# SD.net
KiCad netlist of a schematic drawn in Altium Designer
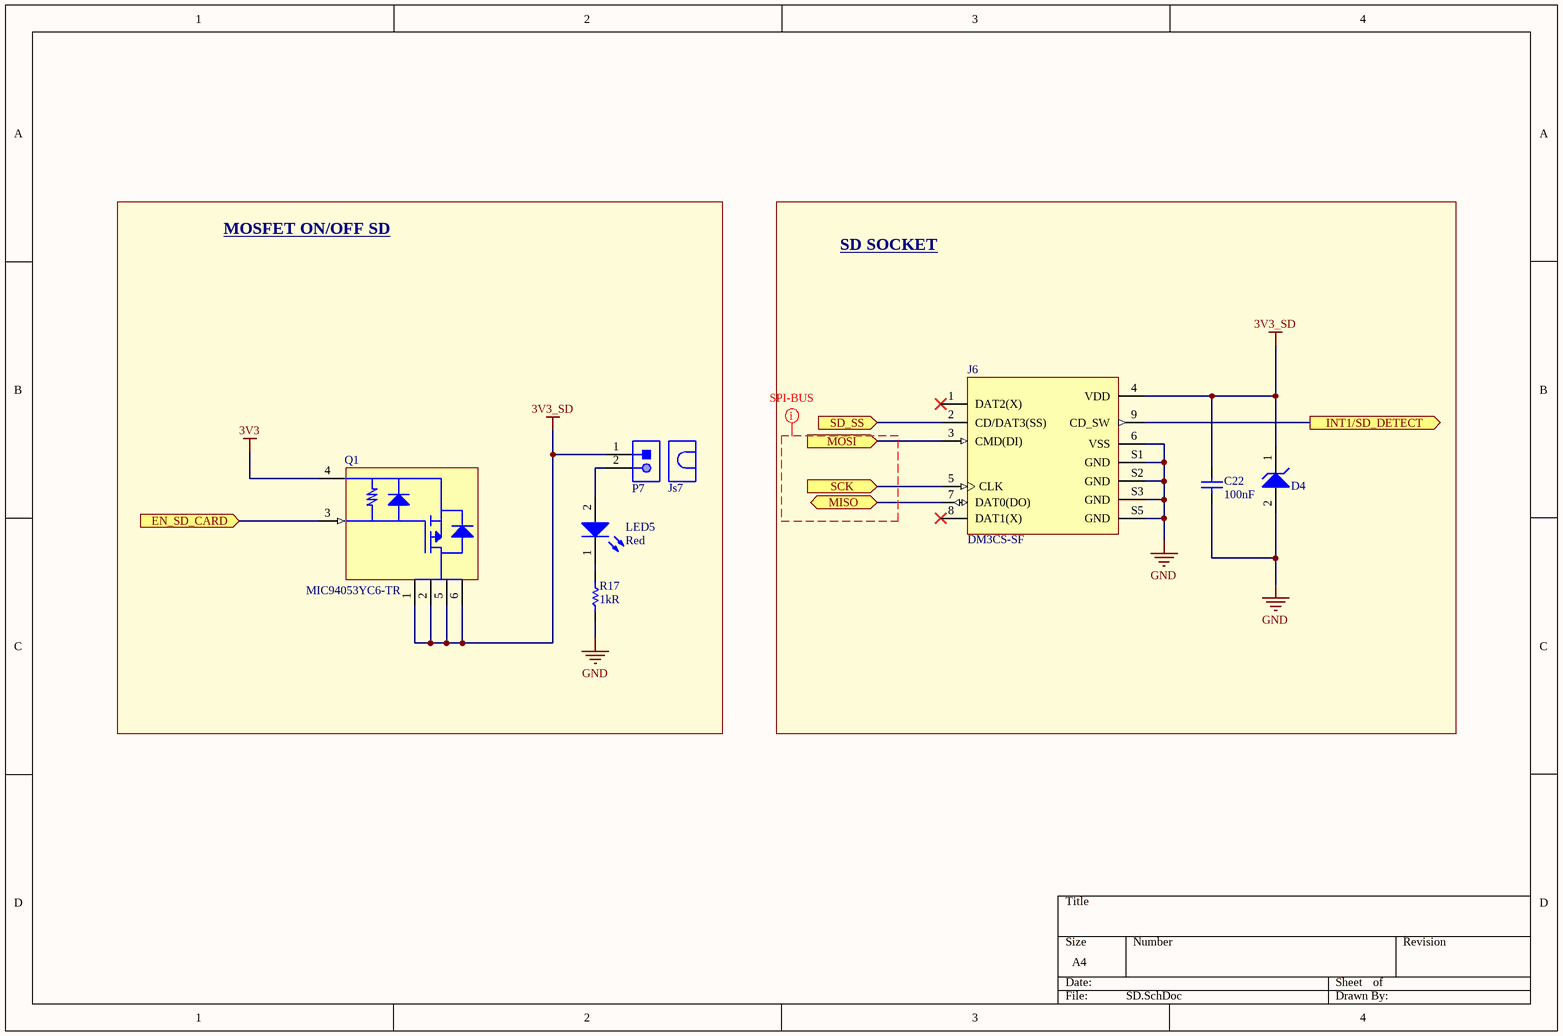
[diagram p0: SD.SchDoc]

(export (version "E")
  (design (tool "Eeschema 10.0.6"))
  (components
    (comp (ref "C22")
      (value "100nF")
      (footprint "Cap 0805 (2012 Metric)")
      (fields
        (field (name "MANUFACTURER") "Yageo")
        (field (name "MANUFACTURER PART NUMBER") "CC0805ZRY5V9BB104")
        (field (name "TOLERANCE") "80%")
      )
      (libsource (lib "Daniel_Integrated_Library") (part "Capacitor"))
    )
    (comp (ref "D4")
      (value "Diode")
      (footprint "Diode SOD123")
      (description "DIODE GEN PURP 75V 150MA 0603")
      (fields
        (field (name "MANUFACTURER") "Taiwan Semiconductor")
        (field (name "MANUFACTURER PART NUMBER") "TS4148CRZG")
      )
      (libsource (lib "Daniel_Integrated_Library") (part "Diode"))
    )
    (comp (ref "J6")
      (value "DM3CS-SF")
      (footprint "SDHolder")
      (description "10 (8 + 2) Position Card Connector Secure Digital - microSD™ Surface Mount, Right Angle Gold")
      (fields (field (name "MANUFACTURER") "Hirose"))
      (libsource (lib "Daniel_Integrated_Library") (part "SDHolder"))
    )
    (comp (ref "Js7")
      (value "Jumper (2x1)")
      (footprint "Header JMP 2x1")
      (description "2 (1 x 2) Position Shunt Connector Black Open Top 0.100\" (2.54mm) Gold")
      (fields
        (field (name "MANUFACTURER") "Sullins")
        (field (name "MANUFACTURER PART NUMBER") "QPC02SXGN-RC")
      )
      (libsource (lib "Daniel_Integrated_Library") (part "Jumper (2x1)"))
    )
    (comp (ref "LED5")
      (value "Red")
      (footprint "LED 0805(2012 METRIC)")
      (description "SMD LED red 2.4 V 0805, 150080RS75000, Würth Elektronik")
      (fields
        (field (name "MANUFACTURER") "Wurth Electronics")
        (field (name "MANUFACTURER PART NUMBER") "150080RS75000")
      )
      (libsource (lib "Daniel_Integrated_Library") (part "LED"))
    )
    (comp (ref "P7")
      (value "Header 2x1")
      (footprint "Header 2x1")
      (description "Connector Header Through Hole 2 position 0.100\" (2.54mm)")
      (fields
        (field (name "MANUFACTURER") "Amphenol FCI")
        (field (name "MANUFACTURER PART NUMBER") "68001-402HLF")
      )
      (libsource (lib "Daniel_Integrated_Library") (part "Header 2x1"))
    )
    (comp (ref "Q1")
      (value "MIC94053YC6-TR")
      (footprint "SC-70-6")
      (description "P-Channel 6V 2A (Ta) 270mW (Ta) Surface Mount SC-70-6")
      (fields (field (name "MANUFACTURER") "Microchip"))
      (libsource (lib "Daniel_Integrated_Library") (part "TransistorMosfet(Load)"))
    )
    (comp (ref "R17")
      (value "1kR")
      (footprint "Res 0805 (2012 Metric)")
      (description "RES 1K OHM 1% 1/4W 0805")
      (fields
        (field (name "MANUFACTURER") "Stackpole Electronics")
        (field (name "MANUFACTURER PART NUMBER") "RNCP0805FTD1K00")
      )
      (libsource (lib "Daniel_Integrated_Library") (part "Resistor"))
    )
  )
  (nets
    (net (code "1") (name "/EN_SD_CARD") (class "Default")
      (node (ref "Q1") (pin "3") (pinfunction "G_3") (pintype "input"))
    )
    (net (code "2") (name "/INT1{slash}SD_DETECT") (class "Default")
      (node (ref "J6") (pin "9") (pinfunction "CD_SW_9") (pintype "output"))
    )
    (net (code "3") (name "/MISO") (class "Default")
      (node (ref "J6") (pin "7") (pinfunction "DAT0(DO)_7") (pintype "bidirectional"))
    )
    (net (code "4") (name "/MOSI") (class "Default")
      (node (ref "J6") (pin "3") (pinfunction "CMD(DI)_3") (pintype "input"))
    )
    (net (code "5") (name "/SCK") (class "Default")
      (node (ref "J6") (pin "5") (pinfunction "CLK_5") (pintype "input"))
    )
    (net (code "6") (name "/SD_SS") (class "Default")
      (node (ref "J6") (pin "2") (pinfunction "CD/DAT3(SS)_2") (pintype "passive"))
    )
    (net (code "7") (name "3V3") (class "Default")
      (node (ref "Q1") (pin "4") (pinfunction "S_4") (pintype "passive"))
    )
    (net (code "8") (name "3V3_SD") (class "Default")
      (node (ref "C22") (pin "1") (pinfunction "1_1") (pintype "passive"))
      (node (ref "D4") (pin "1") (pinfunction "K_1") (pintype "passive"))
      (node (ref "J6") (pin "4") (pinfunction "VDD_4") (pintype "passive"))
      (node (ref "P7") (pin "1") (pinfunction "1_1") (pintype "passive"))
      (node (ref "Q1") (pin "1") (pinfunction "D_1") (pintype "passive"))
      (node (ref "Q1") (pin "2") (pinfunction "D_2") (pintype "passive"))
      (node (ref "Q1") (pin "5") (pinfunction "D_5") (pintype "passive"))
      (node (ref "Q1") (pin "6") (pinfunction "D_6") (pintype "passive"))
    )
    (net (code "9") (name "GND") (class "Default")
      (node (ref "C22") (pin "2") (pinfunction "2_2") (pintype "passive"))
      (node (ref "D4") (pin "2") (pinfunction "A_2") (pintype "passive"))
      (node (ref "J6") (pin "6") (pinfunction "VSS_6") (pintype "passive"))
      (node (ref "J6") (pin "S1") (pinfunction "GND_S1") (pintype "passive"))
      (node (ref "J6") (pin "S2") (pinfunction "GND_S2") (pintype "passive"))
      (node (ref "J6") (pin "S3") (pinfunction "GND_S3") (pintype "passive"))
      (node (ref "J6") (pin "S5") (pinfunction "GND_S5") (pintype "passive"))
      (node (ref "R17") (pin "2") (pinfunction "2_2") (pintype "passive"))
    )
    (net (code "10") (name "Net-(LED5-A)") (class "Default")
      (node (ref "LED5") (pin "2") (pinfunction "A_2") (pintype "passive"))
      (node (ref "P7") (pin "2") (pinfunction "2_2") (pintype "passive"))
    )
    (net (code "11") (name "Net-(LED5-K)") (class "Default")
      (node (ref "LED5") (pin "1") (pinfunction "K_1") (pintype "passive"))
      (node (ref "R17") (pin "1") (pinfunction "1_1") (pintype "passive"))
    )
    (net (code "12") (name "unconnected-(J6-DAT1(X)-Pad8)") (class "Default")
      (node (ref "J6") (pin "8") (pinfunction "DAT1(X)_8") (pintype "passive+no_connect"))
    )
    (net (code "13") (name "unconnected-(J6-DAT2(X)-Pad1)") (class "Default")
      (node (ref "J6") (pin "1") (pinfunction "DAT2(X)_1") (pintype "passive+no_connect"))
    )
  )
)
